# PCIe.net
KiCad netlist of a schematic drawn in Altium Designer
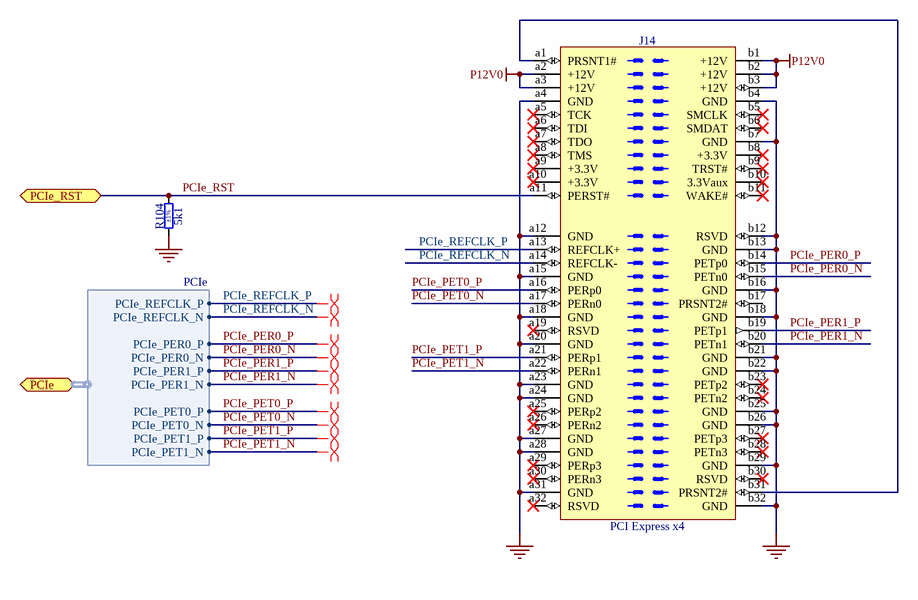
[diagram p0: PCIe.SchDoc]

(export (version "E")
  (design (tool "Eeschema 10.0.6"))
  (components
    (comp (ref "J14")
      (value "PCI Express x4")
      (footprint "PCI Express x4")
      (description "64 contacts Board Eddge PCI Express x4 Connector")
      (fields (field (name "MANUFACTURER") "PCI-SIG") (field (name "AUTHOR") "CERN DEM JLC"))
      (libsource (lib "Connectors") (part "PCI Express x4 Male"))
    )
    (comp (ref "R104")
      (value "5k1")
      (footprint "RESC1005X40N")
      (description "Resistor - 1%")
      (fields
        (field (name "TOLERANCE") "±1%")
        (field (name "PART NUMBER") "R0402_5K1_1%_0.0625W_100PPM")
        (field (name "POWER") "0.0625W")
        (field (name "AUTHOR") "CERN DEM JLC")
      )
      (libsource (lib "Resistors") (part "Resistor - 1%"))
    )
  )
  (nets
    (net (code "2") (name "/PCIe_PER0_N") (class "Default")
      (node (ref "J14") (pin "b15") (pinfunction "PETn0_b15") (pintype "bidirectional"))
    )
    (net (code "3") (name "/PCIe_PER0_P") (class "Default")
      (node (ref "J14") (pin "b14") (pinfunction "PETp0_b14") (pintype "bidirectional"))
    )
    (net (code "4") (name "/PCIe_PER1_N") (class "Default")
      (node (ref "J14") (pin "b20") (pinfunction "PETn1_b20") (pintype "bidirectional"))
    )
    (net (code "5") (name "/PCIe_PER1_P") (class "Default")
      (node (ref "J14") (pin "b19") (pinfunction "PETp1_b19") (pintype "output"))
    )
    (net (code "6") (name "/PCIe_PET0_N") (class "Default")
      (node (ref "J14") (pin "a17") (pinfunction "PERn0_a17") (pintype "bidirectional"))
    )
    (net (code "7") (name "/PCIe_PET0_P") (class "Default")
      (node (ref "J14") (pin "a16") (pinfunction "PERp0_a16") (pintype "bidirectional"))
    )
    (net (code "8") (name "/PCIe_PET1_N") (class "Default")
      (node (ref "J14") (pin "a22") (pinfunction "PERn1_a22") (pintype "bidirectional"))
    )
    (net (code "9") (name "/PCIe_PET1_P") (class "Default")
      (node (ref "J14") (pin "a21") (pinfunction "PERp1_a21") (pintype "bidirectional"))
    )
    (net (code "10") (name "/PCIe_REFCLK_N") (class "Default")
      (node (ref "J14") (pin "a14") (pinfunction "REFCLK-_a14") (pintype "bidirectional"))
    )
    (net (code "11") (name "/PCIe_REFCLK_P") (class "Default")
      (node (ref "J14") (pin "a13") (pinfunction "REFCLK+_a13") (pintype "bidirectional"))
    )
    (net (code "12") (name "/PCIe_RST") (class "Default")
      (node (ref "J14") (pin "a11") (pinfunction "PERST#_a11") (pintype "bidirectional"))
      (node (ref "R104") (pin "2") (pinfunction "2_2") (pintype "passive"))
    )
    (net (code "14") (name "GND") (class "Default")
      (node (ref "J14") (pin "a12") (pinfunction "GND_a12") (pintype "power_in"))
      (node (ref "J14") (pin "a15") (pinfunction "GND_a15") (pintype "power_in"))
      (node (ref "J14") (pin "a18") (pinfunction "GND_a18") (pintype "power_in"))
      (node (ref "J14") (pin "a20") (pinfunction "GND_a20") (pintype "power_in"))
      (node (ref "J14") (pin "a23") (pinfunction "GND_a23") (pintype "power_in"))
      (node (ref "J14") (pin "a24") (pinfunction "GND_a24") (pintype "power_in"))
      (node (ref "J14") (pin "a27") (pinfunction "GND_a27") (pintype "power_in"))
      (node (ref "J14") (pin "a28") (pinfunction "GND_a28") (pintype "power_in"))
      (node (ref "J14") (pin "a31") (pinfunction "GND_a31") (pintype "power_in"))
      (node (ref "J14") (pin "a4") (pinfunction "GND_a4") (pintype "power_in"))
      (node (ref "J14") (pin "b12") (pinfunction "RSVD_b12") (pintype "bidirectional"))
      (node (ref "J14") (pin "b13") (pinfunction "GND_b13") (pintype "power_in"))
      (node (ref "J14") (pin "b16") (pinfunction "GND_b16") (pintype "power_in"))
      (node (ref "J14") (pin "b18") (pinfunction "GND_b18") (pintype "power_in"))
      (node (ref "J14") (pin "b21") (pinfunction "GND_b21") (pintype "power_in"))
      (node (ref "J14") (pin "b22") (pinfunction "GND_b22") (pintype "power_in"))
      (node (ref "J14") (pin "b25") (pinfunction "GND_b25") (pintype "power_in"))
      (node (ref "J14") (pin "b26") (pinfunction "GND_b26") (pintype "power_in"))
      (node (ref "J14") (pin "b29") (pinfunction "GND_b29") (pintype "power_in"))
      (node (ref "J14") (pin "b32") (pinfunction "GND_b32") (pintype "power_in"))
      (node (ref "J14") (pin "b4") (pinfunction "GND_b4") (pintype "power_in"))
      (node (ref "J14") (pin "b7") (pinfunction "GND_b7") (pintype "power_in"))
      (node (ref "R104") (pin "1") (pinfunction "1_1") (pintype "passive"))
    )
    (net (code "15") (name "Net-(J14-PRSNT1#)") (class "Default")
      (node (ref "J14") (pin "a1") (pinfunction "PRSNT1#_a1") (pintype "bidirectional"))
      (node (ref "J14") (pin "b31") (pinfunction "PRSNT2#_b31") (pintype "bidirectional"))
    )
    (net (code "16") (name "P12V0") (class "Default")
      (node (ref "J14") (pin "a2") (pinfunction "+12V_a2") (pintype "power_in"))
      (node (ref "J14") (pin "a3") (pinfunction "+12V_a3") (pintype "power_in"))
      (node (ref "J14") (pin "b1") (pinfunction "+12V_b1") (pintype "power_in"))
      (node (ref "J14") (pin "b2") (pinfunction "+12V_b2") (pintype "power_in"))
      (node (ref "J14") (pin "b3") (pinfunction "+12V_b3") (pintype "bidirectional"))
    )
    (net (code "17") (name "unconnected-(J14-+3.3V-Pada9)") (class "Default")
      (node (ref "J14") (pin "a9") (pinfunction "+3.3V_a9") (pintype "power_in+no_connect"))
    )
    (net (code "18") (name "unconnected-(J14-+3.3V-Pada10)") (class "Default")
      (node (ref "J14") (pin "a10") (pinfunction "+3.3V_a10") (pintype "power_in+no_connect"))
    )
    (net (code "19") (name "unconnected-(J14-+3.3V-Padb8)") (class "Default")
      (node (ref "J14") (pin "b8") (pinfunction "+3.3V_b8") (pintype "power_in+no_connect"))
    )
    (net (code "20") (name "unconnected-(J14-3.3Vaux-Padb10)") (class "Default")
      (node (ref "J14") (pin "b10") (pinfunction "3.3Vaux_b10") (pintype "power_in+no_connect"))
    )
    (net (code "21") (name "unconnected-(J14-PERn2-Pada26)") (class "Default")
      (node (ref "J14") (pin "a26") (pinfunction "PERn2_a26") (pintype "bidirectional+no_connect"))
    )
    (net (code "22") (name "unconnected-(J14-PERn3-Pada30)") (class "Default")
      (node (ref "J14") (pin "a30") (pinfunction "PERn3_a30") (pintype "bidirectional+no_connect"))
    )
    (net (code "23") (name "unconnected-(J14-PERp2-Pada25)") (class "Default")
      (node (ref "J14") (pin "a25") (pinfunction "PERp2_a25") (pintype "bidirectional+no_connect"))
    )
    (net (code "24") (name "unconnected-(J14-PERp3-Pada29)") (class "Default")
      (node (ref "J14") (pin "a29") (pinfunction "PERp3_a29") (pintype "bidirectional+no_connect"))
    )
    (net (code "25") (name "unconnected-(J14-PETn2-Padb24)") (class "Default")
      (node (ref "J14") (pin "b24") (pinfunction "PETn2_b24") (pintype "bidirectional+no_connect"))
    )
    (net (code "26") (name "unconnected-(J14-PETn3-Padb28)") (class "Default")
      (node (ref "J14") (pin "b28") (pinfunction "PETn3_b28") (pintype "bidirectional+no_connect"))
    )
    (net (code "27") (name "unconnected-(J14-PETp2-Padb23)") (class "Default")
      (node (ref "J14") (pin "b23") (pinfunction "PETp2_b23") (pintype "bidirectional+no_connect"))
    )
    (net (code "28") (name "unconnected-(J14-PETp3-Padb27)") (class "Default")
      (node (ref "J14") (pin "b27") (pinfunction "PETp3_b27") (pintype "bidirectional+no_connect"))
    )
    (net (code "29") (name "unconnected-(J14-PRSNT2#-Padb17)") (class "Default")
      (node (ref "J14") (pin "b17") (pinfunction "PRSNT2#_b17") (pintype "bidirectional"))
    )
    (net (code "30") (name "unconnected-(J14-RSVD-Pada19)") (class "Default")
      (node (ref "J14") (pin "a19") (pinfunction "RSVD_a19") (pintype "bidirectional+no_connect"))
    )
    (net (code "31") (name "unconnected-(J14-RSVD-Pada32)") (class "Default")
      (node (ref "J14") (pin "a32") (pinfunction "RSVD_a32") (pintype "bidirectional+no_connect"))
    )
    (net (code "32") (name "unconnected-(J14-RSVD-Padb30)") (class "Default")
      (node (ref "J14") (pin "b30") (pinfunction "RSVD_b30") (pintype "bidirectional+no_connect"))
    )
    (net (code "33") (name "unconnected-(J14-SMCLK-Padb5)") (class "Default")
      (node (ref "J14") (pin "b5") (pinfunction "SMCLK_b5") (pintype "bidirectional+no_connect"))
    )
    (net (code "34") (name "unconnected-(J14-SMDAT-Padb6)") (class "Default")
      (node (ref "J14") (pin "b6") (pinfunction "SMDAT_b6") (pintype "bidirectional+no_connect"))
    )
    (net (code "35") (name "unconnected-(J14-TCK-Pada5)") (class "Default")
      (node (ref "J14") (pin "a5") (pinfunction "TCK_a5") (pintype "bidirectional+no_connect"))
    )
    (net (code "36") (name "unconnected-(J14-TDI-Pada6)") (class "Default")
      (node (ref "J14") (pin "a6") (pinfunction "TDI_a6") (pintype "bidirectional+no_connect"))
    )
    (net (code "37") (name "unconnected-(J14-TDO-Pada7)") (class "Default")
      (node (ref "J14") (pin "a7") (pinfunction "TDO_a7") (pintype "bidirectional+no_connect"))
    )
    (net (code "38") (name "unconnected-(J14-TMS-Pada8)") (class "Default")
      (node (ref "J14") (pin "a8") (pinfunction "TMS_a8") (pintype "bidirectional+no_connect"))
    )
    (net (code "39") (name "unconnected-(J14-TRST#-Padb9)") (class "Default")
      (node (ref "J14") (pin "b9") (pinfunction "TRST#_b9") (pintype "bidirectional+no_connect"))
    )
    (net (code "40") (name "unconnected-(J14-WAKE#-Padb11)") (class "Default")
      (node (ref "J14") (pin "b11") (pinfunction "WAKE#_b11") (pintype "bidirectional+no_connect"))
    )
  )
)
